# MCU.net
KiCad netlist of a schematic drawn in Altium Designer
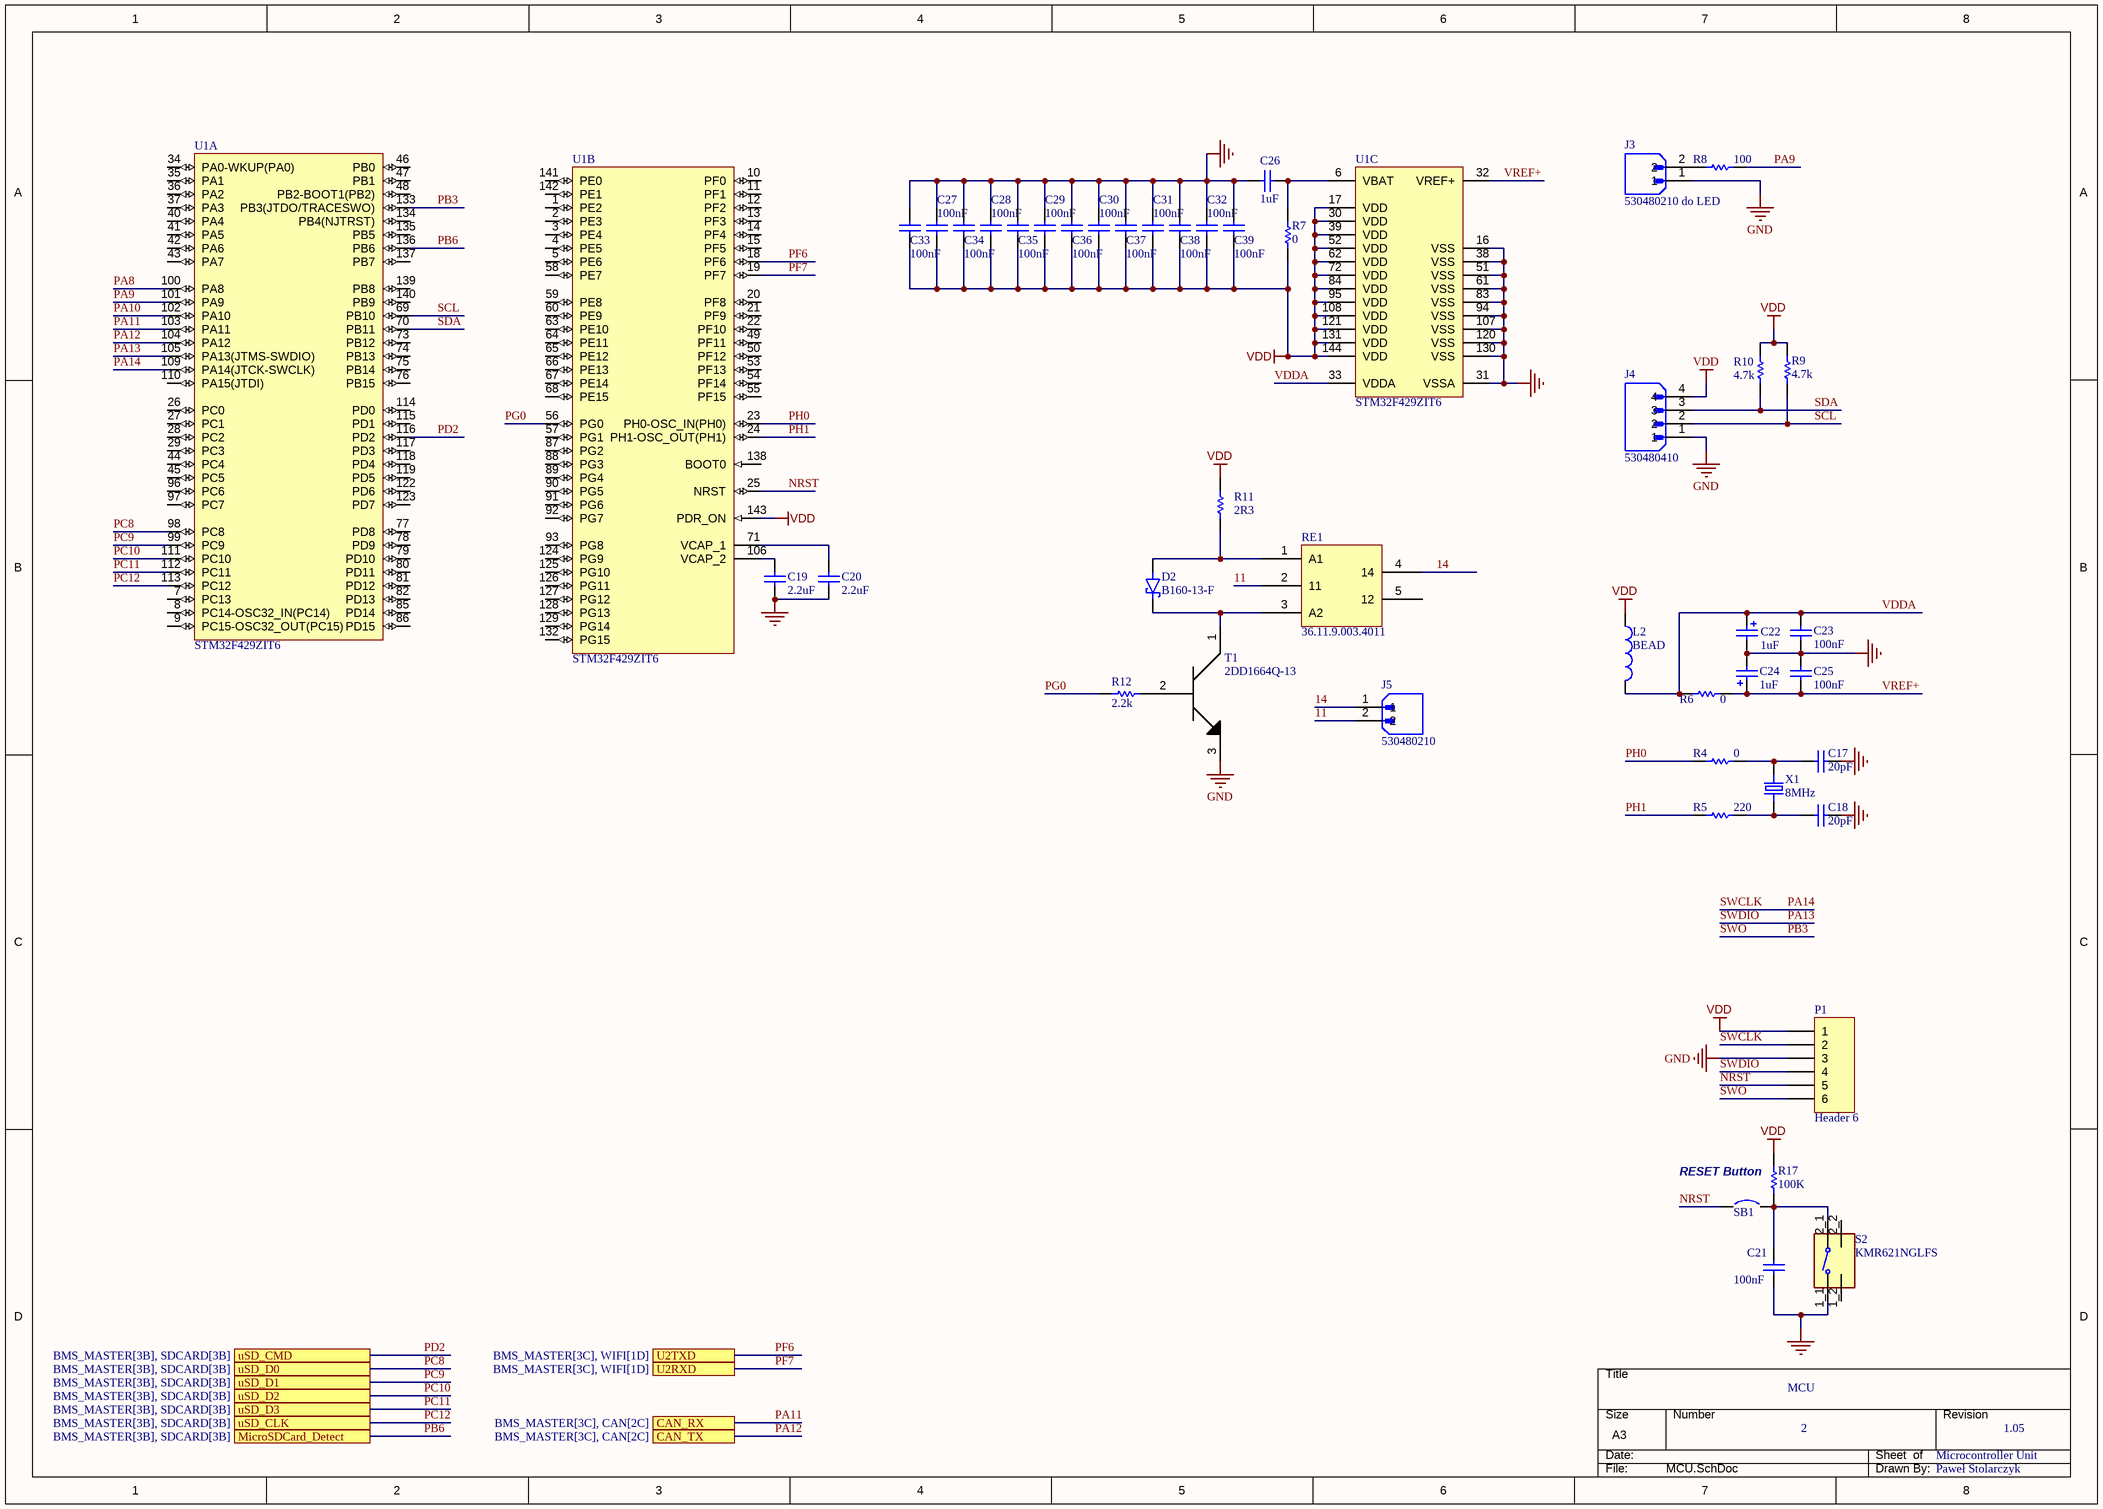
[diagram p0: MCU.SchDoc]

(export (version "E")
  (design (tool "Eeschema 10.0.6"))
  (components
    (comp (ref "C17")
      (value "20pF")
      (footprint "0402")
      (description "Capacitor 0402 / 0603 / 0805")
      (libsource (lib "MCD_TOOLS") (part "Capacitor_ST"))
    )
    (comp (ref "C18")
      (value "20pF")
      (footprint "0402")
      (description "Capacitor 0402 / 0603 / 0805")
      (libsource (lib "MCD_TOOLS") (part "Capacitor_ST"))
    )
    (comp (ref "C19")
      (value "2.2uF")
      (footprint "C1206")
      (description "Low ESR Ceramic Capacitor (X7R)")
      (libsource (lib "MCD_TOOLS") (part "Cap Low ESR"))
    )
    (comp (ref "C20")
      (value "2.2uF")
      (footprint "C1206")
      (description "Low ESR Ceramic Capacitor (X7R)")
      (libsource (lib "MCD_TOOLS") (part "Cap Low ESR"))
    )
    (comp (ref "C21")
      (value "100nF")
      (footprint "0402")
      (description "Capacitor 0402 / 0603 / 0805")
      (libsource (lib "MCD_TOOLS") (part "Capacitor_ST"))
    )
    (comp (ref "C22")
      (value "1uF")
      (footprint "C1206")
      (description "Polarized Capacitor (Radial)")
      (fields (field (name "PUBLISHER") "Altium Limited"))
      (libsource (lib "Miscellaneous Devices") (part "Cap Pol1"))
    )
    (comp (ref "C23")
      (value "100nF")
      (footprint "0402")
      (description "Capacitor 0402 / 0603 / 0805")
      (libsource (lib "MCD_TOOLS") (part "Capacitor_ST"))
    )
    (comp (ref "C24")
      (value "1uF")
      (footprint "C1206")
      (description "Polarized Capacitor (Radial)")
      (fields (field (name "PUBLISHER") "Altium Limited"))
      (libsource (lib "Miscellaneous Devices") (part "Cap Pol1"))
    )
    (comp (ref "C25")
      (value "100nF")
      (footprint "0402")
      (description "Capacitor 0402 / 0603 / 0805")
      (libsource (lib "MCD_TOOLS") (part "Capacitor_ST"))
    )
    (comp (ref "C26")
      (value "1uF")
      (footprint "C1206")
      (description "Capacitor 0402 / 0603 / 0805")
      (libsource (lib "MCD_TOOLS") (part "Capacitor_ST"))
    )
    (comp (ref "C27")
      (value "100nF")
      (footprint "0402")
      (description "Capacitor 0402 / 0603 / 0805")
      (libsource (lib "MCD_TOOLS") (part "Capacitor_ST"))
    )
    (comp (ref "C28")
      (value "100nF")
      (footprint "0402")
      (description "Capacitor 0402 / 0603 / 0805")
      (libsource (lib "MCD_TOOLS") (part "Capacitor_ST"))
    )
    (comp (ref "C29")
      (value "100nF")
      (footprint "0402")
      (description "Capacitor 0402 / 0603 / 0805")
      (libsource (lib "MCD_TOOLS") (part "Capacitor_ST"))
    )
    (comp (ref "C30")
      (value "100nF")
      (footprint "0402")
      (description "Capacitor 0402 / 0603 / 0805")
      (libsource (lib "MCD_TOOLS") (part "Capacitor_ST"))
    )
    (comp (ref "C31")
      (value "100nF")
      (footprint "0402")
      (description "Capacitor 0402 / 0603 / 0805")
      (libsource (lib "MCD_TOOLS") (part "Capacitor_ST"))
    )
    (comp (ref "C32")
      (value "100nF")
      (footprint "0402")
      (description "Capacitor 0402 / 0603 / 0805")
      (libsource (lib "MCD_TOOLS") (part "Capacitor_ST"))
    )
    (comp (ref "C33")
      (value "100nF")
      (footprint "0402")
      (description "Capacitor 0402 / 0603 / 0805")
      (libsource (lib "MCD_TOOLS") (part "Capacitor_ST"))
    )
    (comp (ref "C34")
      (value "100nF")
      (footprint "0402")
      (description "Capacitor 0402 / 0603 / 0805")
      (libsource (lib "MCD_TOOLS") (part "Capacitor_ST"))
    )
    (comp (ref "C35")
      (value "100nF")
      (footprint "0402")
      (description "Capacitor 0402 / 0603 / 0805")
      (libsource (lib "MCD_TOOLS") (part "Capacitor_ST"))
    )
    (comp (ref "C36")
      (value "100nF")
      (footprint "0402")
      (description "Capacitor 0402 / 0603 / 0805")
      (libsource (lib "MCD_TOOLS") (part "Capacitor_ST"))
    )
    (comp (ref "C37")
      (value "100nF")
      (footprint "0402")
      (description "Capacitor 0402 / 0603 / 0805")
      (libsource (lib "MCD_TOOLS") (part "Capacitor_ST"))
    )
    (comp (ref "C38")
      (value "100nF")
      (footprint "0402")
      (description "Capacitor 0402 / 0603 / 0805")
      (libsource (lib "MCD_TOOLS") (part "Capacitor_ST"))
    )
    (comp (ref "C39")
      (value "100nF")
      (footprint "0402")
      (description "Capacitor 0402 / 0603 / 0805")
      (libsource (lib "MCD_TOOLS") (part "Capacitor_ST"))
    )
    (comp (ref "D2")
      (value "B160-13-F")
      (footprint "DIODE_B160-13-F")
      (description "Diode Schottky 60V 1A Surface Mount SMA")
      (fields (field (name "MF") "Diodes Inc."))
      (libsource (lib "B160-13-F") (part "B160-13-F"))
    )
    (comp (ref "J3")
      (value "530480210 do LED")
      (footprint "MOLEX_530480210")
      (description "Conn Shrouded Header (4 Sides) HDR 2 POS 1.25mm Solder RA Side Entry Thru-Hole PicoBladeâ„¢ Tray")
      (fields (field (name "MF") "Molex") (field (name "MP") "530480210"))
      (libsource (lib "") (part "530480210_1"))
    )
    (comp (ref "J4")
      (value "530480410")
      (footprint "MOLEX_530480410")
      (libsource (lib "530480410") (part "530480410"))
    )
    (comp (ref "J5")
      (value "530480210")
      (footprint "MOLEX_530480210")
      (description "Conn Shrouded Header (4 Sides) HDR 2 POS 1.25mm Solder RA Side Entry Thru-Hole PicoBladeâ„¢ Tray")
      (fields (field (name "MF") "Molex"))
      (libsource (lib "530480210") (part "530480210"))
    )
    (comp (ref "L2")
      (value "BEAD")
      (footprint "0402")
      (description "Inductor")
      (fields (field (name "PUBLISHER") "Altium Limited"))
      (libsource (lib "MCD_TOOLS") (part "Inductor"))
    )
    (comp (ref "P1")
      (value "Header 6")
      (footprint "HDR1X6")
      (description "Header, 6-Pin")
      (fields (field (name "PUBLISHER") "Altium Limited"))
      (libsource (lib "Miscellaneous Connectors") (part "Header 6"))
    )
    (comp (ref "R4")
      (value "0")
      (footprint "0402")
      (description "Resistor 0402 / 0603 / 0805")
      (libsource (lib "MCD_TOOLS") (part "Resistor_ST"))
    )
    (comp (ref "R5")
      (value "220")
      (footprint "0402")
      (description "Resistor 0402 / 0603 / 0805")
      (libsource (lib "MCD_TOOLS") (part "Resistor_ST"))
    )
    (comp (ref "R6")
      (value "0")
      (footprint "0402")
      (description "Resistor 0402 / 0603 / 0805")
      (libsource (lib "MCD_TOOLS") (part "Resistor_ST"))
    )
    (comp (ref "R7")
      (value "0")
      (footprint "0402")
      (description "Resistor 0402 / 0603 / 0805")
      (libsource (lib "MCD_TOOLS") (part "Resistor_ST"))
    )
    (comp (ref "R8")
      (value "100")
      (footprint "0402")
      (description "Resistor 0402 / 0603 / 0805")
      (libsource (lib "MCD_TOOLS") (part "Resistor_ST"))
    )
    (comp (ref "R9")
      (value "4.7k")
      (footprint "0402")
      (description "Resistor 0402 / 0603 / 0805")
      (libsource (lib "MCD_TOOLS") (part "Resistor_ST"))
    )
    (comp (ref "R10")
      (value "4.7k")
      (footprint "0402")
      (description "Resistor 0402 / 0603 / 0805")
      (libsource (lib "MCD_TOOLS") (part "Resistor_ST"))
    )
    (comp (ref "R11")
      (value "2R3")
      (footprint "C1206")
      (description "Resistor")
      (fields (field (name "Comment") "Res1") (field (name "PUBLISHER") "Altium Limited"))
      (libsource (lib "Miscellaneous Devices") (part "Res1"))
    )
    (comp (ref "R12")
      (value "2.2k")
      (footprint "0402")
      (description "Resistor 0402 / 0603 / 0805")
      (libsource (lib "MCD_TOOLS") (part "Resistor_ST"))
    )
    (comp (ref "R17")
      (value "100K")
      (footprint "0402")
      (description "Resistor 0402 / 0603 / 0805")
      (libsource (lib "MCD_TOOLS") (part "Resistor_ST"))
    )
    (comp (ref "RE1")
      (value "36.11.9.003.4011")
      (footprint "36.11.9.003.4011")
      (description "Przekaźnik: elektromagnetyczny; SPDT; Ucewki : 3VDC; 15A; PCB; 25Ω")
      (libsource (lib "36.11.9.003.4011") (part "36.11.9.003.4011"))
    )
    (comp (ref "S2")
      (value "KMR621NGLFS")
      (footprint "SW_KMR621NGLFS")
      (description "Tactile Switch SPST-NO Top Actuated Surface Mount")
      (fields (field (name "MF") "C&K") (field (name "MP") "KMR621NG LFS"))
      (libsource (lib "KMR621NGLFS") (part "KMR621NGLFS"))
    )
    (comp (ref "SB1")
      (value "Circuit Breaker")
      (footprint "0402")
      (fields (field (name "PUBLISHER") "Altium Limited"))
      (libsource (lib "MB915") (part "Circuit Breaker"))
    )
    (comp (ref "T1")
      (value "2DD1664Q-13")
      (footprint "SOT150P410X160-3N")
      (description "Transistor: NPN; bipolar; 32V; 1A; 1W; SOT89; automotive industry")
      (libsource (lib "2DD1664Q-13") (part "2DD1664Q-13"))
    )
    (comp (ref "U1")
      (value "STM32F429ZIT6")
      (footprint "STM-LQFP144_N")
      (fields (field (name "MANUFACTURER") "STMicroelectronics"))
      (libsource (lib "STMicroelectronics STM32 F4") (part "STM32F429ZIT6"))
    )
    (comp (ref "X1")
      (value "8MHz")
      (footprint "8M-49S-SR")
      (description "8MHz; ±30ppm; 20pF; THT; HC49-S")
      (fields (field (name "MF") "ECS Inc.") (field (name "MP") "ECS-160-20-4VX"))
      (libsource (lib "8M-49S-SR") (part "8M-49S-SR"))
    )
  )
  (nets
    (net (code "1") (name "/11") (class "Default")
      (node (ref "J5") (pin "2") (pinfunction "2_2") (pintype "passive"))
      (node (ref "RE1") (pin "2") (pinfunction "11_2") (pintype "passive"))
    )
    (net (code "2") (name "/14") (class "Default")
      (node (ref "J5") (pin "1") (pinfunction "1_1") (pintype "passive"))
      (node (ref "RE1") (pin "4") (pinfunction "14_4") (pintype "passive"))
    )
    (net (code "3") (name "/NRST") (class "Default")
      (node (ref "P1") (pin "5") (pinfunction "5_5") (pintype "passive"))
      (node (ref "SB1") (pin "1") (pinfunction "1_1") (pintype "passive"))
      (node (ref "U1") (pin "25") (pinfunction "NRST_25") (pintype "bidirectional"))
    )
    (net (code "4") (name "/PA8") (class "Default")
      (node (ref "U1") (pin "100") (pinfunction "PA8_100") (pintype "bidirectional"))
    )
    (net (code "5") (name "/PA9") (class "Default")
      (node (ref "R8") (pin "2") (pinfunction "2_2") (pintype "passive"))
      (node (ref "U1") (pin "101") (pinfunction "PA9_101") (pintype "bidirectional"))
    )
    (net (code "6") (name "/PA10") (class "Default")
      (node (ref "U1") (pin "102") (pinfunction "PA10_102") (pintype "bidirectional"))
    )
    (net (code "7") (name "/PA11") (class "Default")
      (node (ref "U1") (pin "103") (pinfunction "PA11_103") (pintype "bidirectional"))
    )
    (net (code "8") (name "/PA12") (class "Default")
      (node (ref "U1") (pin "104") (pinfunction "PA12_104") (pintype "bidirectional"))
    )
    (net (code "9") (name "/PA13") (class "Default")
      (node (ref "P1") (pin "4") (pinfunction "4_4") (pintype "passive"))
      (node (ref "U1") (pin "105") (pinfunction "PA13(JTMS-SWDIO)_105") (pintype "bidirectional"))
    )
    (net (code "10") (name "/PA14") (class "Default")
      (node (ref "P1") (pin "2") (pinfunction "2_2") (pintype "passive"))
      (node (ref "U1") (pin "109") (pinfunction "PA14(JTCK-SWCLK)_109") (pintype "bidirectional"))
    )
    (net (code "11") (name "/PB3") (class "Default")
      (node (ref "P1") (pin "6") (pinfunction "6_6") (pintype "passive"))
      (node (ref "U1") (pin "133") (pinfunction "PB3(JTDO/TRACESWO)_133") (pintype "bidirectional"))
    )
    (net (code "12") (name "/PB6") (class "Default")
      (node (ref "U1") (pin "136") (pinfunction "PB6_136") (pintype "bidirectional"))
    )
    (net (code "13") (name "/PC8") (class "Default")
      (node (ref "U1") (pin "98") (pinfunction "PC8_98") (pintype "bidirectional"))
    )
    (net (code "14") (name "/PC9") (class "Default")
      (node (ref "U1") (pin "99") (pinfunction "PC9_99") (pintype "bidirectional"))
    )
    (net (code "15") (name "/PC10") (class "Default")
      (node (ref "U1") (pin "111") (pinfunction "PC10_111") (pintype "bidirectional"))
    )
    (net (code "16") (name "/PC11") (class "Default")
      (node (ref "U1") (pin "112") (pinfunction "PC11_112") (pintype "bidirectional"))
    )
    (net (code "17") (name "/PC12") (class "Default")
      (node (ref "U1") (pin "113") (pinfunction "PC12_113") (pintype "bidirectional"))
    )
    (net (code "18") (name "/PD2") (class "Default")
      (node (ref "U1") (pin "116") (pinfunction "PD2_116") (pintype "bidirectional"))
    )
    (net (code "19") (name "/PF6") (class "Default")
      (node (ref "U1") (pin "18") (pinfunction "PF6_18") (pintype "bidirectional"))
    )
    (net (code "20") (name "/PF7") (class "Default")
      (node (ref "U1") (pin "19") (pinfunction "PF7_19") (pintype "bidirectional"))
    )
    (net (code "21") (name "/PG0") (class "Default")
      (node (ref "R12") (pin "1") (pinfunction "1_1") (pintype "passive"))
      (node (ref "U1") (pin "56") (pinfunction "PG0_56") (pintype "bidirectional"))
    )
    (net (code "22") (name "/PH0") (class "Default")
      (node (ref "R4") (pin "1") (pinfunction "1_1") (pintype "passive"))
      (node (ref "U1") (pin "23") (pinfunction "PH0-OSC_IN(PH0)_23") (pintype "bidirectional"))
    )
    (net (code "23") (name "/PH1") (class "Default")
      (node (ref "R5") (pin "1") (pinfunction "1_1") (pintype "passive"))
      (node (ref "U1") (pin "24") (pinfunction "PH1-OSC_OUT(PH1)_24") (pintype "bidirectional"))
    )
    (net (code "24") (name "/SCL") (class "Default")
      (node (ref "J4") (pin "2") (pinfunction "2_2") (pintype "passive"))
      (node (ref "R9") (pin "2") (pinfunction "2_2") (pintype "passive"))
      (node (ref "U1") (pin "69") (pinfunction "PB10_69") (pintype "bidirectional"))
    )
    (net (code "25") (name "/SDA") (class "Default")
      (node (ref "J4") (pin "3") (pinfunction "3_3") (pintype "passive"))
      (node (ref "R10") (pin "2") (pinfunction "2_2") (pintype "passive"))
      (node (ref "U1") (pin "70") (pinfunction "PB11_70") (pintype "bidirectional"))
    )
    (net (code "26") (name "/VDDA") (class "Default")
      (node (ref "C22") (pin "1") (pinfunction "1_1") (pintype "passive"))
      (node (ref "C23") (pin "2") (pinfunction "2_2") (pintype "passive"))
      (node (ref "L2") (pin "2") (pinfunction "2_2") (pintype "passive"))
      (node (ref "R6") (pin "1") (pinfunction "1_1") (pintype "passive"))
      (node (ref "U1") (pin "33") (pinfunction "VDDA_33") (pintype "power_in"))
    )
    (net (code "27") (name "/VREF+") (class "Default")
      (node (ref "C24") (pin "1") (pinfunction "1_1") (pintype "passive"))
      (node (ref "C25") (pin "1") (pinfunction "1_1") (pintype "passive"))
      (node (ref "R6") (pin "2") (pinfunction "2_2") (pintype "passive"))
      (node (ref "U1") (pin "32") (pinfunction "VREF+_32") (pintype "power_in"))
    )
    (net (code "28") (name "GND") (class "Default")
      (node (ref "C17") (pin "2") (pinfunction "2_2") (pintype "passive"))
      (node (ref "C18") (pin "2") (pinfunction "2_2") (pintype "passive"))
      (node (ref "C19") (pin "2") (pinfunction "2_2") (pintype "passive"))
      (node (ref "C20") (pin "2") (pinfunction "2_2") (pintype "passive"))
      (node (ref "C21") (pin "1") (pinfunction "1_1") (pintype "passive"))
      (node (ref "C22") (pin "2") (pinfunction "2_2") (pintype "passive"))
      (node (ref "C23") (pin "1") (pinfunction "1_1") (pintype "passive"))
      (node (ref "C24") (pin "2") (pinfunction "2_2") (pintype "passive"))
      (node (ref "C25") (pin "2") (pinfunction "2_2") (pintype "passive"))
      (node (ref "C26") (pin "1") (pinfunction "1_1") (pintype "passive"))
      (node (ref "C27") (pin "2") (pinfunction "2_2") (pintype "passive"))
      (node (ref "C28") (pin "2") (pinfunction "2_2") (pintype "passive"))
      (node (ref "C29") (pin "2") (pinfunction "2_2") (pintype "passive"))
      (node (ref "C30") (pin "2") (pinfunction "2_2") (pintype "passive"))
      (node (ref "C31") (pin "2") (pinfunction "2_2") (pintype "passive"))
      (node (ref "C32") (pin "2") (pinfunction "2_2") (pintype "passive"))
      (node (ref "C33") (pin "2") (pinfunction "2_2") (pintype "passive"))
      (node (ref "C34") (pin "2") (pinfunction "2_2") (pintype "passive"))
      (node (ref "C35") (pin "2") (pinfunction "2_2") (pintype "passive"))
      (node (ref "C36") (pin "2") (pinfunction "2_2") (pintype "passive"))
      (node (ref "C37") (pin "2") (pinfunction "2_2") (pintype "passive"))
      (node (ref "C38") (pin "2") (pinfunction "2_2") (pintype "passive"))
      (node (ref "C39") (pin "2") (pinfunction "2_2") (pintype "passive"))
      (node (ref "J3") (pin "1") (pinfunction "1_1") (pintype "passive"))
      (node (ref "J4") (pin "1") (pinfunction "1_1") (pintype "passive"))
      (node (ref "P1") (pin "3") (pinfunction "3_3") (pintype "passive"))
      (node (ref "S2") (pin "1_1") (pinfunction "1_1_1") (pintype "passive"))
      (node (ref "T1") (pin "3") (pinfunction "3_3") (pintype "passive"))
      (node (ref "U1") (pin "107") (pinfunction "VSS_107") (pintype "power_in"))
      (node (ref "U1") (pin "120") (pinfunction "VSS_120") (pintype "power_in"))
      (node (ref "U1") (pin "130") (pinfunction "VSS_130") (pintype "power_in"))
      (node (ref "U1") (pin "16") (pinfunction "VSS_16") (pintype "power_in"))
      (node (ref "U1") (pin "31") (pinfunction "VSSA_31") (pintype "power_in"))
      (node (ref "U1") (pin "38") (pinfunction "VSS_38") (pintype "power_in"))
      (node (ref "U1") (pin "51") (pinfunction "VSS_51") (pintype "power_in"))
      (node (ref "U1") (pin "61") (pinfunction "VSS_61") (pintype "power_in"))
      (node (ref "U1") (pin "83") (pinfunction "VSS_83") (pintype "power_in"))
      (node (ref "U1") (pin "94") (pinfunction "VSS_94") (pintype "power_in"))
    )
    (net (code "29") (name "Net-(C17-Pad1)") (class "Default")
      (node (ref "C17") (pin "1") (pinfunction "1_1") (pintype "passive"))
      (node (ref "R4") (pin "2") (pinfunction "2_2") (pintype "passive"))
      (node (ref "X1") (pin "2") (pinfunction "2_2") (pintype "passive"))
    )
    (net (code "30") (name "Net-(C18-Pad1)") (class "Default")
      (node (ref "C18") (pin "1") (pinfunction "1_1") (pintype "passive"))
      (node (ref "R5") (pin "2") (pinfunction "2_2") (pintype "passive"))
      (node (ref "X1") (pin "1") (pinfunction "1_1") (pintype "passive"))
    )
    (net (code "31") (name "Net-(C21-Pad2)") (class "Default")
      (node (ref "C21") (pin "2") (pinfunction "2_2") (pintype "passive"))
      (node (ref "R17") (pin "1") (pinfunction "1_1") (pintype "passive"))
      (node (ref "S2") (pin "2_1") (pinfunction "2_2_1") (pintype "passive"))
      (node (ref "SB1") (pin "2") (pinfunction "2_2") (pintype "passive"))
    )
    (net (code "32") (name "Net-(D2-A)") (class "Default")
      (node (ref "D2") (pin "2") (pinfunction "A_2") (pintype "passive"))
      (node (ref "R11") (pin "1") (pinfunction "1_1") (pintype "passive"))
      (node (ref "RE1") (pin "1") (pinfunction "A1_1") (pintype "passive"))
    )
    (net (code "33") (name "Net-(D2-C)") (class "Default")
      (node (ref "D2") (pin "1") (pinfunction "C_1") (pintype "passive"))
      (node (ref "RE1") (pin "3") (pinfunction "A2_3") (pintype "passive"))
      (node (ref "T1") (pin "1") (pinfunction "1_1") (pintype "passive"))
    )
    (net (code "34") (name "Net-(J3-Pad2)") (class "Default")
      (node (ref "J3") (pin "2") (pinfunction "2_2") (pintype "passive"))
      (node (ref "R8") (pin "1") (pinfunction "1_1") (pintype "passive"))
    )
    (net (code "35") (name "Net-(R12-Pad2)") (class "Default")
      (node (ref "R12") (pin "2") (pinfunction "2_2") (pintype "passive"))
      (node (ref "T1") (pin "2") (pinfunction "2_2") (pintype "passive"))
    )
    (net (code "36") (name "Net-(U1B-VCAP_1)") (class "Default")
      (node (ref "C20") (pin "1") (pinfunction "1_1") (pintype "passive"))
      (node (ref "U1") (pin "71") (pinfunction "VCAP_1_71") (pintype "power_in"))
    )
    (net (code "37") (name "Net-(U1B-VCAP_2)") (class "Default")
      (node (ref "C19") (pin "1") (pinfunction "1_1") (pintype "passive"))
      (node (ref "U1") (pin "106") (pinfunction "VCAP_2_106") (pintype "power_in"))
    )
    (net (code "38") (name "Net-(U1C-VBAT)") (class "Default")
      (node (ref "C26") (pin "2") (pinfunction "2_2") (pintype "passive"))
      (node (ref "R7") (pin "2") (pinfunction "2_2") (pintype "passive"))
      (node (ref "U1") (pin "6") (pinfunction "VBAT_6") (pintype "power_in"))
    )
    (net (code "39") (name "VDD") (class "Default")
      (node (ref "C27") (pin "1") (pinfunction "1_1") (pintype "passive"))
      (node (ref "C28") (pin "1") (pinfunction "1_1") (pintype "passive"))
      (node (ref "C29") (pin "1") (pinfunction "1_1") (pintype "passive"))
      (node (ref "C30") (pin "1") (pinfunction "1_1") (pintype "passive"))
      (node (ref "C31") (pin "1") (pinfunction "1_1") (pintype "passive"))
      (node (ref "C32") (pin "1") (pinfunction "1_1") (pintype "passive"))
      (node (ref "C33") (pin "1") (pinfunction "1_1") (pintype "passive"))
      (node (ref "C34") (pin "1") (pinfunction "1_1") (pintype "passive"))
      (node (ref "C35") (pin "1") (pinfunction "1_1") (pintype "passive"))
      (node (ref "C36") (pin "1") (pinfunction "1_1") (pintype "passive"))
      (node (ref "C37") (pin "1") (pinfunction "1_1") (pintype "passive"))
      (node (ref "C38") (pin "1") (pinfunction "1_1") (pintype "passive"))
      (node (ref "C39") (pin "1") (pinfunction "1_1") (pintype "passive"))
      (node (ref "J4") (pin "4") (pinfunction "4_4") (pintype "passive"))
      (node (ref "L2") (pin "1") (pinfunction "1_1") (pintype "passive"))
      (node (ref "P1") (pin "1") (pinfunction "1_1") (pintype "passive"))
      (node (ref "R10") (pin "1") (pinfunction "1_1") (pintype "passive"))
      (node (ref "R11") (pin "2") (pinfunction "2_2") (pintype "passive"))
      (node (ref "R17") (pin "2") (pinfunction "2_2") (pintype "passive"))
      (node (ref "R7") (pin "1") (pinfunction "1_1") (pintype "passive"))
      (node (ref "R9") (pin "1") (pinfunction "1_1") (pintype "passive"))
      (node (ref "U1") (pin "108") (pinfunction "VDD_108") (pintype "power_in"))
      (node (ref "U1") (pin "121") (pinfunction "VDD_121") (pintype "power_in"))
      (node (ref "U1") (pin "131") (pinfunction "VDD_131") (pintype "power_in"))
      (node (ref "U1") (pin "143") (pinfunction "PDR_ON_143") (pintype "input"))
      (node (ref "U1") (pin "144") (pinfunction "VDD_144") (pintype "power_in"))
      (node (ref "U1") (pin "17") (pinfunction "VDD_17") (pintype "power_in"))
      (node (ref "U1") (pin "30") (pinfunction "VDD_30") (pintype "power_in"))
      (node (ref "U1") (pin "39") (pinfunction "VDD_39") (pintype "power_in"))
      (node (ref "U1") (pin "52") (pinfunction "VDD_52") (pintype "power_in"))
      (node (ref "U1") (pin "62") (pinfunction "VDD_62") (pintype "power_in"))
      (node (ref "U1") (pin "72") (pinfunction "VDD_72") (pintype "power_in"))
      (node (ref "U1") (pin "84") (pinfunction "VDD_84") (pintype "power_in"))
      (node (ref "U1") (pin "95") (pinfunction "VDD_95") (pintype "power_in"))
    )
    (net (code "40") (name "unconnected-(RE1-12-Pad5)") (class "Default")
      (node (ref "RE1") (pin "5") (pinfunction "12_5") (pintype "passive"))
    )
    (net (code "41") (name "unconnected-(S2-1-Pad1_2)") (class "Default")
      (node (ref "S2") (pin "1_2") (pinfunction "1_1_2") (pintype "passive"))
    )
    (net (code "42") (name "unconnected-(S2-2-Pad2_2)") (class "Default")
      (node (ref "S2") (pin "2_2") (pinfunction "2_2_2") (pintype "passive"))
    )
    (net (code "43") (name "unconnected-(U1A-PA0-WKUP(PA0)-Pad34)") (class "Default")
      (node (ref "U1") (pin "34") (pinfunction "PA0-WKUP(PA0)_34") (pintype "bidirectional"))
    )
    (net (code "44") (name "unconnected-(U1A-PA1-Pad35)") (class "Default")
      (node (ref "U1") (pin "35") (pinfunction "PA1_35") (pintype "bidirectional"))
    )
    (net (code "45") (name "unconnected-(U1A-PA2-Pad36)") (class "Default")
      (node (ref "U1") (pin "36") (pinfunction "PA2_36") (pintype "bidirectional"))
    )
    (net (code "46") (name "unconnected-(U1A-PA3-Pad37)") (class "Default")
      (node (ref "U1") (pin "37") (pinfunction "PA3_37") (pintype "bidirectional"))
    )
    (net (code "47") (name "unconnected-(U1A-PA4-Pad40)") (class "Default")
      (node (ref "U1") (pin "40") (pinfunction "PA4_40") (pintype "bidirectional"))
    )
    (net (code "48") (name "unconnected-(U1A-PA5-Pad41)") (class "Default")
      (node (ref "U1") (pin "41") (pinfunction "PA5_41") (pintype "bidirectional"))
    )
    (net (code "49") (name "unconnected-(U1A-PA6-Pad42)") (class "Default")
      (node (ref "U1") (pin "42") (pinfunction "PA6_42") (pintype "bidirectional"))
    )
    (net (code "50") (name "unconnected-(U1A-PA7-Pad43)") (class "Default")
      (node (ref "U1") (pin "43") (pinfunction "PA7_43") (pintype "bidirectional"))
    )
    (net (code "51") (name "unconnected-(U1A-PA15(JTDI)-Pad110)") (class "Default")
      (node (ref "U1") (pin "110") (pinfunction "PA15(JTDI)_110") (pintype "bidirectional"))
    )
    (net (code "52") (name "unconnected-(U1A-PB0-Pad46)") (class "Default")
      (node (ref "U1") (pin "46") (pinfunction "PB0_46") (pintype "bidirectional"))
    )
    (net (code "53") (name "unconnected-(U1A-PB1-Pad47)") (class "Default")
      (node (ref "U1") (pin "47") (pinfunction "PB1_47") (pintype "bidirectional"))
    )
    (net (code "54") (name "unconnected-(U1A-PB2-BOOT1(PB2)-Pad48)") (class "Default")
      (node (ref "U1") (pin "48") (pinfunction "PB2-BOOT1(PB2)_48") (pintype "bidirectional"))
    )
    (net (code "55") (name "unconnected-(U1A-PB4(NJTRST)-Pad134)") (class "Default")
      (node (ref "U1") (pin "134") (pinfunction "PB4(NJTRST)_134") (pintype "bidirectional"))
    )
    (net (code "56") (name "unconnected-(U1A-PB5-Pad135)") (class "Default")
      (node (ref "U1") (pin "135") (pinfunction "PB5_135") (pintype "bidirectional"))
    )
    (net (code "57") (name "unconnected-(U1A-PB7-Pad137)") (class "Default")
      (node (ref "U1") (pin "137") (pinfunction "PB7_137") (pintype "bidirectional"))
    )
    (net (code "58") (name "unconnected-(U1A-PB8-Pad139)") (class "Default")
      (node (ref "U1") (pin "139") (pinfunction "PB8_139") (pintype "bidirectional"))
    )
    (net (code "59") (name "unconnected-(U1A-PB9-Pad140)") (class "Default")
      (node (ref "U1") (pin "140") (pinfunction "PB9_140") (pintype "bidirectional"))
    )
    (net (code "60") (name "unconnected-(U1A-PB12-Pad73)") (class "Default")
      (node (ref "U1") (pin "73") (pinfunction "PB12_73") (pintype "bidirectional"))
    )
    (net (code "61") (name "unconnected-(U1A-PB13-Pad74)") (class "Default")
      (node (ref "U1") (pin "74") (pinfunction "PB13_74") (pintype "bidirectional"))
    )
    (net (code "62") (name "unconnected-(U1A-PB14-Pad75)") (class "Default")
      (node (ref "U1") (pin "75") (pinfunction "PB14_75") (pintype "bidirectional"))
    )
    (net (code "63") (name "unconnected-(U1A-PB15-Pad76)") (class "Default")
      (node (ref "U1") (pin "76") (pinfunction "PB15_76") (pintype "bidirectional"))
    )
    (net (code "64") (name "unconnected-(U1A-PC0-Pad26)") (class "Default")
      (node (ref "U1") (pin "26") (pinfunction "PC0_26") (pintype "bidirectional"))
    )
    (net (code "65") (name "unconnected-(U1A-PC1-Pad27)") (class "Default")
      (node (ref "U1") (pin "27") (pinfunction "PC1_27") (pintype "bidirectional"))
    )
    (net (code "66") (name "unconnected-(U1A-PC2-Pad28)") (class "Default")
      (node (ref "U1") (pin "28") (pinfunction "PC2_28") (pintype "bidirectional"))
    )
    (net (code "67") (name "unconnected-(U1A-PC3-Pad29)") (class "Default")
      (node (ref "U1") (pin "29") (pinfunction "PC3_29") (pintype "bidirectional"))
    )
    (net (code "68") (name "unconnected-(U1A-PC4-Pad44)") (class "Default")
      (node (ref "U1") (pin "44") (pinfunction "PC4_44") (pintype "bidirectional"))
    )
    (net (code "69") (name "unconnected-(U1A-PC5-Pad45)") (class "Default")
      (node (ref "U1") (pin "45") (pinfunction "PC5_45") (pintype "bidirectional"))
    )
    (net (code "70") (name "unconnected-(U1A-PC6-Pad96)") (class "Default")
      (node (ref "U1") (pin "96") (pinfunction "PC6_96") (pintype "bidirectional"))
    )
    (net (code "71") (name "unconnected-(U1A-PC7-Pad97)") (class "Default")
      (node (ref "U1") (pin "97") (pinfunction "PC7_97") (pintype "bidirectional"))
    )
    (net (code "72") (name "unconnected-(U1A-PC13-Pad7)") (class "Default")
      (node (ref "U1") (pin "7") (pinfunction "PC13_7") (pintype "bidirectional"))
    )
    (net (code "73") (name "unconnected-(U1A-PC14-OSC32_IN(PC14)-Pad8)") (class "Default")
      (node (ref "U1") (pin "8") (pinfunction "PC14-OSC32_IN(PC14)_8") (pintype "bidirectional"))
    )
    (net (code "74") (name "unconnected-(U1A-PC15-OSC32_OUT(PC15)-Pad9)") (class "Default")
      (node (ref "U1") (pin "9") (pinfunction "PC15-OSC32_OUT(PC15)_9") (pintype "bidirectional"))
    )
    (net (code "75") (name "unconnected-(U1A-PD0-Pad114)") (class "Default")
      (node (ref "U1") (pin "114") (pinfunction "PD0_114") (pintype "bidirectional"))
    )
    (net (code "76") (name "unconnected-(U1A-PD1-Pad115)") (class "Default")
      (node (ref "U1") (pin "115") (pinfunction "PD1_115") (pintype "bidirectional"))
    )
    (net (code "77") (name "unconnected-(U1A-PD3-Pad117)") (class "Default")
      (node (ref "U1") (pin "117") (pinfunction "PD3_117") (pintype "bidirectional"))
    )
    (net (code "78") (name "unconnected-(U1A-PD4-Pad118)") (class "Default")
      (node (ref "U1") (pin "118") (pinfunction "PD4_118") (pintype "bidirectional"))
    )
    (net (code "79") (name "unconnected-(U1A-PD5-Pad119)") (class "Default")
      (node (ref "U1") (pin "119") (pinfunction "PD5_119") (pintype "bidirectional"))
    )
    (net (code "80") (name "unconnected-(U1A-PD6-Pad122)") (class "Default")
      (node (ref "U1") (pin "122") (pinfunction "PD6_122") (pintype "bidirectional"))
    )
    (net (code "81") (name "unconnected-(U1A-PD7-Pad123)") (class "Default")
      (node (ref "U1") (pin "123") (pinfunction "PD7_123") (pintype "bidirectional"))
    )
    (net (code "82") (name "unconnected-(U1A-PD8-Pad77)") (class "Default")
      (node (ref "U1") (pin "77") (pinfunction "PD8_77") (pintype "bidirectional"))
    )
    (net (code "83") (name "unconnected-(U1A-PD9-Pad78)") (class "Default")
      (node (ref "U1") (pin "78") (pinfunction "PD9_78") (pintype "bidirectional"))
    )
    (net (code "84") (name "unconnected-(U1A-PD10-Pad79)") (class "Default")
      (node (ref "U1") (pin "79") (pinfunction "PD10_79") (pintype "bidirectional"))
    )
    (net (code "85") (name "unconnected-(U1A-PD11-Pad80)") (class "Default")
      (node (ref "U1") (pin "80") (pinfunction "PD11_80") (pintype "bidirectional"))
    )
    (net (code "86") (name "unconnected-(U1A-PD12-Pad81)") (class "Default")
      (node (ref "U1") (pin "81") (pinfunction "PD12_81") (pintype "bidirectional"))
    )
    (net (code "87") (name "unconnected-(U1A-PD13-Pad82)") (class "Default")
      (node (ref "U1") (pin "82") (pinfunction "PD13_82") (pintype "bidirectional"))
    )
    (net (code "88") (name "unconnected-(U1A-PD14-Pad85)") (class "Default")
      (node (ref "U1") (pin "85") (pinfunction "PD14_85") (pintype "bidirectional"))
    )
    (net (code "89") (name "unconnected-(U1A-PD15-Pad86)") (class "Default")
      (node (ref "U1") (pin "86") (pinfunction "PD15_86") (pintype "bidirectional"))
    )
    (net (code "90") (name "unconnected-(U1B-BOOT0-Pad138)") (class "Default")
      (node (ref "U1") (pin "138") (pinfunction "BOOT0_138") (pintype "input"))
    )
    (net (code "91") (name "unconnected-(U1B-PE0-Pad141)") (class "Default")
      (node (ref "U1") (pin "141") (pinfunction "PE0_141") (pintype "bidirectional"))
    )
    (net (code "92") (name "unconnected-(U1B-PE1-Pad142)") (class "Default")
      (node (ref "U1") (pin "142") (pinfunction "PE1_142") (pintype "bidirectional"))
    )
    (net (code "93") (name "unconnected-(U1B-PE2-Pad1)") (class "Default")
      (node (ref "U1") (pin "1") (pinfunction "PE2_1") (pintype "bidirectional"))
    )
    (net (code "94") (name "unconnected-(U1B-PE3-Pad2)") (class "Default")
      (node (ref "U1") (pin "2") (pinfunction "PE3_2") (pintype "bidirectional"))
    )
    (net (code "95") (name "unconnected-(U1B-PE4-Pad3)") (class "Default")
      (node (ref "U1") (pin "3") (pinfunction "PE4_3") (pintype "bidirectional"))
    )
    (net (code "96") (name "unconnected-(U1B-PE5-Pad4)") (class "Default")
      (node (ref "U1") (pin "4") (pinfunction "PE5_4") (pintype "bidirectional"))
    )
    (net (code "97") (name "unconnected-(U1B-PE6-Pad5)") (class "Default")
      (node (ref "U1") (pin "5") (pinfunction "PE6_5") (pintype "bidirectional"))
    )
    (net (code "98") (name "unconnected-(U1B-PE7-Pad58)") (class "Default")
      (node (ref "U1") (pin "58") (pinfunction "PE7_58") (pintype "bidirectional"))
    )
    (net (code "99") (name "unconnected-(U1B-PE8-Pad59)") (class "Default")
      (node (ref "U1") (pin "59") (pinfunction "PE8_59") (pintype "bidirectional"))
    )
    (net (code "100") (name "unconnected-(U1B-PE9-Pad60)") (class "Default")
      (node (ref "U1") (pin "60") (pinfunction "PE9_60") (pintype "bidirectional"))
    )
    (net (code "101") (name "unconnected-(U1B-PE10-Pad63)") (class "Default")
      (node (ref "U1") (pin "63") (pinfunction "PE10_63") (pintype "bidirectional"))
    )
    (net (code "102") (name "unconnected-(U1B-PE11-Pad64)") (class "Default")
      (node (ref "U1") (pin "64") (pinfunction "PE11_64") (pintype "bidirectional"))
    )
    (net (code "103") (name "unconnected-(U1B-PE12-Pad65)") (class "Default")
      (node (ref "U1") (pin "65") (pinfunction "PE12_65") (pintype "bidirectional"))
    )
    (net (code "104") (name "unconnected-(U1B-PE13-Pad66)") (class "Default")
      (node (ref "U1") (pin "66") (pinfunction "PE13_66") (pintype "bidirectional"))
    )
    (net (code "105") (name "unconnected-(U1B-PE14-Pad67)") (class "Default")
      (node (ref "U1") (pin "67") (pinfunction "PE14_67") (pintype "bidirectional"))
    )
    (net (code "106") (name "unconnected-(U1B-PE15-Pad68)") (class "Default")
      (node (ref "U1") (pin "68") (pinfunction "PE15_68") (pintype "bidirectional"))
    )
    (net (code "107") (name "unconnected-(U1B-PF0-Pad10)") (class "Default")
      (node (ref "U1") (pin "10") (pinfunction "PF0_10") (pintype "bidirectional"))
    )
    (net (code "108") (name "unconnected-(U1B-PF1-Pad11)") (class "Default")
      (node (ref "U1") (pin "11") (pinfunction "PF1_11") (pintype "bidirectional"))
    )
    (net (code "109") (name "unconnected-(U1B-PF2-Pad12)") (class "Default")
      (node (ref "U1") (pin "12") (pinfunction "PF2_12") (pintype "bidirectional"))
    )
    (net (code "110") (name "unconnected-(U1B-PF3-Pad13)") (class "Default")
      (node (ref "U1") (pin "13") (pinfunction "PF3_13") (pintype "bidirectional"))
    )
    (net (code "111") (name "unconnected-(U1B-PF4-Pad14)") (class "Default")
      (node (ref "U1") (pin "14") (pinfunction "PF4_14") (pintype "bidirectional"))
    )
    (net (code "112") (name "unconnected-(U1B-PF5-Pad15)") (class "Default")
      (node (ref "U1") (pin "15") (pinfunction "PF5_15") (pintype "bidirectional"))
    )
    (net (code "113") (name "unconnected-(U1B-PF8-Pad20)") (class "Default")
      (node (ref "U1") (pin "20") (pinfunction "PF8_20") (pintype "bidirectional"))
    )
    (net (code "114") (name "unconnected-(U1B-PF9-Pad21)") (class "Default")
      (node (ref "U1") (pin "21") (pinfunction "PF9_21") (pintype "bidirectional"))
    )
    (net (code "115") (name "unconnected-(U1B-PF10-Pad22)") (class "Default")
      (node (ref "U1") (pin "22") (pinfunction "PF10_22") (pintype "bidirectional"))
    )
    (net (code "116") (name "unconnected-(U1B-PF11-Pad49)") (class "Default")
      (node (ref "U1") (pin "49") (pinfunction "PF11_49") (pintype "bidirectional"))
    )
    (net (code "117") (name "unconnected-(U1B-PF12-Pad50)") (class "Default")
      (node (ref "U1") (pin "50") (pinfunction "PF12_50") (pintype "bidirectional"))
    )
    (net (code "118") (name "unconnected-(U1B-PF13-Pad53)") (class "Default")
      (node (ref "U1") (pin "53") (pinfunction "PF13_53") (pintype "bidirectional"))
    )
    (net (code "119") (name "unconnected-(U1B-PF14-Pad54)") (class "Default")
      (node (ref "U1") (pin "54") (pinfunction "PF14_54") (pintype "bidirectional"))
    )
    (net (code "120") (name "unconnected-(U1B-PF15-Pad55)") (class "Default")
      (node (ref "U1") (pin "55") (pinfunction "PF15_55") (pintype "bidirectional"))
    )
    (net (code "121") (name "unconnected-(U1B-PG1-Pad57)") (class "Default")
      (node (ref "U1") (pin "57") (pinfunction "PG1_57") (pintype "bidirectional"))
    )
    (net (code "122") (name "unconnected-(U1B-PG2-Pad87)") (class "Default")
      (node (ref "U1") (pin "87") (pinfunction "PG2_87") (pintype "bidirectional"))
    )
    (net (code "123") (name "unconnected-(U1B-PG3-Pad88)") (class "Default")
      (node (ref "U1") (pin "88") (pinfunction "PG3_88") (pintype "bidirectional"))
    )
    (net (code "124") (name "unconnected-(U1B-PG4-Pad89)") (class "Default")
      (node (ref "U1") (pin "89") (pinfunction "PG4_89") (pintype "bidirectional"))
    )
    (net (code "125") (name "unconnected-(U1B-PG5-Pad90)") (class "Default")
      (node (ref "U1") (pin "90") (pinfunction "PG5_90") (pintype "bidirectional"))
    )
    (net (code "126") (name "unconnected-(U1B-PG6-Pad91)") (class "Default")
      (node (ref "U1") (pin "91") (pinfunction "PG6_91") (pintype "bidirectional"))
    )
    (net (code "127") (name "unconnected-(U1B-PG7-Pad92)") (class "Default")
      (node (ref "U1") (pin "92") (pinfunction "PG7_92") (pintype "bidirectional"))
    )
    (net (code "128") (name "unconnected-(U1B-PG8-Pad93)") (class "Default")
      (node (ref "U1") (pin "93") (pinfunction "PG8_93") (pintype "bidirectional"))
    )
    (net (code "129") (name "unconnected-(U1B-PG9-Pad124)") (class "Default")
      (node (ref "U1") (pin "124") (pinfunction "PG9_124") (pintype "bidirectional"))
    )
    (net (code "130") (name "unconnected-(U1B-PG10-Pad125)") (class "Default")
      (node (ref "U1") (pin "125") (pinfunction "PG10_125") (pintype "bidirectional"))
    )
    (net (code "131") (name "unconnected-(U1B-PG11-Pad126)") (class "Default")
      (node (ref "U1") (pin "126") (pinfunction "PG11_126") (pintype "bidirectional"))
    )
    (net (code "132") (name "unconnected-(U1B-PG12-Pad127)") (class "Default")
      (node (ref "U1") (pin "127") (pinfunction "PG12_127") (pintype "bidirectional"))
    )
    (net (code "133") (name "unconnected-(U1B-PG13-Pad128)") (class "Default")
      (node (ref "U1") (pin "128") (pinfunction "PG13_128") (pintype "bidirectional"))
    )
    (net (code "134") (name "unconnected-(U1B-PG14-Pad129)") (class "Default")
      (node (ref "U1") (pin "129") (pinfunction "PG14_129") (pintype "bidirectional"))
    )
    (net (code "135") (name "unconnected-(U1B-PG15-Pad132)") (class "Default")
      (node (ref "U1") (pin "132") (pinfunction "PG15_132") (pintype "bidirectional"))
    )
  )
)
